# Base_SCH.net
KiCad netlist of a schematic drawn in Altium Designer
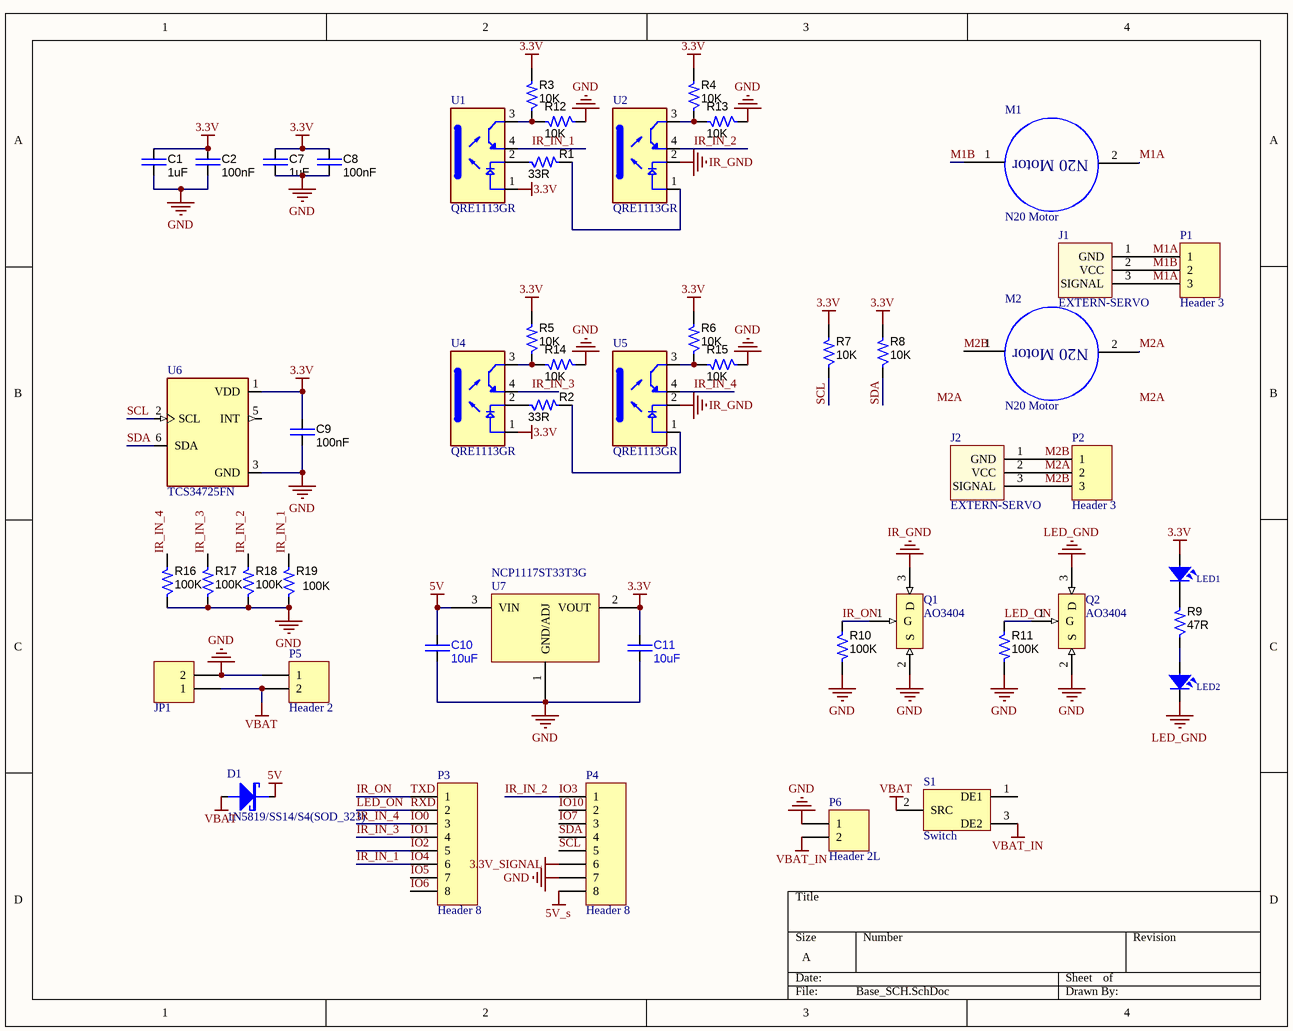
[diagram p0: Base_SCH.SchDoc]

(export (version "E")
  (design (tool "Eeschema 10.0.6"))
  (components
    (comp (ref "C1")
      (value "1uF")
      (footprint "CAPC1608X90N")
      (description "Capacitor SMD Cer 470nF 10% 16V X7R 0603")
      (fields (field (name "TOLERANCE") "±10%"))
      (libsource (lib "WIle_dev_kit") (part "CAP C_0603"))
    )
    (comp (ref "C2")
      (value "100nF")
      (footprint "CAPC1608X90N")
      (description "Capacitor SMD Cer 470nF 10% 16V X7R 0603")
      (fields (field (name "TOLERANCE") "±10%"))
      (libsource (lib "WIle_dev_kit") (part "CAP C_0603"))
    )
    (comp (ref "C7")
      (value "1uF")
      (footprint "CAPC1608X90N")
      (description "Capacitor SMD Cer 470nF 10% 16V X7R 0603")
      (fields (field (name "TOLERANCE") "±10%"))
      (libsource (lib "WIle_dev_kit") (part "CAP C_0603"))
    )
    (comp (ref "C8")
      (value "100nF")
      (footprint "CAPC1608X90N")
      (description "Capacitor SMD Cer 470nF 10% 16V X7R 0603")
      (fields (field (name "TOLERANCE") "±10%"))
      (libsource (lib "WIle_dev_kit") (part "CAP C_0603"))
    )
    (comp (ref "C9")
      (value "100nF")
      (footprint "CAPC1608X90N")
      (description "Capacitor SMD Cer 470nF 10% 16V X7R 0603")
      (fields (field (name "TOLERANCE") "±10%"))
      (libsource (lib "WIle_dev_kit") (part "CAP C_0603"))
    )
    (comp (ref "C10")
      (value "10uF")
      (footprint "CAPC2012X135N")
      (description "Capacitor SMD Cer 1.8nF 10% 50V X7R 0805")
      (fields (field (name "TOLERANCE") "±10%") (field (name "Comment") "approved sub OK"))
      (libsource (lib "WIle_dev_kit") (part "CAP C_0805"))
    )
    (comp (ref "C11")
      (value "10uF")
      (footprint "CAPC2012X135N")
      (description "Capacitor SMD Cer 1.8nF 10% 50V X7R 0805")
      (fields (field (name "TOLERANCE") "±10%") (field (name "Comment") "approved sub OK"))
      (libsource (lib "WIle_dev_kit") (part "CAP C_0805"))
    )
    (comp (ref "D1")
      (value "1N5819/SS14/S4(SOD_323)")
      (footprint "SMT_DIODE_SOD_323")
      (description "Surface mount schottky diode SOD-323(0805) Package")
      (libsource (lib "ad_via") (part "SMT_DIODE_SCHOTTKY_SOD_323"))
    )
    (comp (ref "J1")
      (value "EXTERN-SERVO")
      (footprint "JP3H")
      (libsource (lib "ad_via_motors") (part "EXTERN-SERVO"))
    )
    (comp (ref "J2")
      (value "EXTERN-SERVO")
      (footprint "JP3H")
      (libsource (lib "ad_via_motors") (part "EXTERN-SERVO"))
    )
    (comp (ref "JP1")
      (value "Header 2_1")
      (footprint "HED2")
      (description "Header, 2-Pin")
      (fields (field (name "MANUFACTURER") "Generic Components"))
      (libsource (lib "syhaunguyen") (part "Header 2_1"))
    )
    (comp (ref "LED1")
      (value "LED SMD")
      (footprint "SM-LED-0805-Orange")
      (libsource (lib "WIle_dev_kit") (part "LED SMD 0805"))
    )
    (comp (ref "LED2")
      (value "LED SMD")
      (footprint "SM-LED-0805-Orange")
      (libsource (lib "WIle_dev_kit") (part "LED SMD 0805"))
    )
    (comp (ref "M1")
      (value "N20 Motor")
      (footprint "N20 motor no header")
      (libsource (lib "WIle_dev_kit") (part "N20 Motor"))
    )
    (comp (ref "M2")
      (value "N20 Motor")
      (footprint "N20 motor no header")
      (libsource (lib "WIle_dev_kit") (part "N20 Motor"))
    )
    (comp (ref "P1")
      (value "Header 3")
      (footprint "HDR1X3")
      (description "Header, 3-Pin")
      (fields (field (name "PUBLISHER") "Altium Limited"))
      (libsource (lib "Miscellaneous Connectors") (part "Header 3"))
    )
    (comp (ref "P2")
      (value "Header 3")
      (footprint "HDR1X3")
      (description "Header, 3-Pin")
      (fields (field (name "PUBLISHER") "Altium Limited"))
      (libsource (lib "Miscellaneous Connectors") (part "Header 3"))
    )
    (comp (ref "P3")
      (value "Header 8")
      (footprint "HDR1X8")
      (description "Header, 8-Pin")
      (fields (field (name "PUBLISHER") "Altium Limited"))
      (libsource (lib "Miscellaneous Connectors") (part "Header 8"))
    )
    (comp (ref "P4")
      (value "Header 8")
      (footprint "HDR1X8")
      (description "Header, 8-Pin")
      (fields (field (name "PUBLISHER") "Altium Limited"))
      (libsource (lib "Miscellaneous Connectors") (part "Header 8"))
    )
    (comp (ref "P5")
      (value "Header 2")
      (footprint "HDR1X2")
      (description "Header, 2-Pin")
      (fields (field (name "PUBLISHER") "Altium Limited"))
      (libsource (lib "Miscellaneous Connectors") (part "Header 2"))
    )
    (comp (ref "P6")
      (value "Header 2L")
      (footprint "HDR1X2 - L")
      (description "Header, 2-Pin")
      (fields (field (name "PUBLISHER") "Altium Limited"))
      (libsource (lib "My Library") (part "Header 2L"))
    )
    (comp (ref "Q1") (value "AO3404") (footprint "SOT23-3") (libsource (lib "WIle_dev_kit") (part "AO3404")))
    (comp (ref "Q2") (value "AO3404") (footprint "SOT23-3") (libsource (lib "WIle_dev_kit") (part "AO3404")))
    (comp (ref "R1")
      (value "33R")
      (footprint "RESC1608N_ZERO")
      (description "Resistor SMD chip 0.0 Ohm 0.1W 0603")
      (fields (field (name "TOLERANCE") "±5%"))
      (libsource (lib "WIle_dev_kit") (part "RES_0603"))
    )
    (comp (ref "R2")
      (value "33R")
      (footprint "RESC1608N_ZERO")
      (description "Resistor SMD chip 0.0 Ohm 0.1W 0603")
      (fields (field (name "TOLERANCE") "±5%"))
      (libsource (lib "WIle_dev_kit") (part "RES_0603"))
    )
    (comp (ref "R3")
      (value "10K")
      (footprint "RESC1608N_ZERO")
      (description "Resistor SMD chip 0.0 Ohm 0.1W 0603")
      (fields (field (name "TOLERANCE") "±5%"))
      (libsource (lib "WIle_dev_kit") (part "RES_0603"))
    )
    (comp (ref "R4")
      (value "10K")
      (footprint "RESC1608N_ZERO")
      (description "Resistor SMD chip 0.0 Ohm 0.1W 0603")
      (fields (field (name "TOLERANCE") "±5%"))
      (libsource (lib "WIle_dev_kit") (part "RES_0603"))
    )
    (comp (ref "R5")
      (value "10K")
      (footprint "RESC1608N_ZERO")
      (description "Resistor SMD chip 0.0 Ohm 0.1W 0603")
      (fields (field (name "TOLERANCE") "±5%"))
      (libsource (lib "WIle_dev_kit") (part "RES_0603"))
    )
    (comp (ref "R6")
      (value "10K")
      (footprint "RESC1608N_ZERO")
      (description "Resistor SMD chip 0.0 Ohm 0.1W 0603")
      (fields (field (name "TOLERANCE") "±5%"))
      (libsource (lib "WIle_dev_kit") (part "RES_0603"))
    )
    (comp (ref "R7")
      (value "10K")
      (footprint "RESC1608N_ZERO")
      (description "Resistor SMD chip 0.0 Ohm 0.1W 0603")
      (fields (field (name "TOLERANCE") "±5%"))
      (libsource (lib "WIle_dev_kit") (part "RES_0603"))
    )
    (comp (ref "R8")
      (value "10K")
      (footprint "RESC1608N_ZERO")
      (description "Resistor SMD chip 0.0 Ohm 0.1W 0603")
      (fields (field (name "TOLERANCE") "±5%"))
      (libsource (lib "WIle_dev_kit") (part "RES_0603"))
    )
    (comp (ref "R9")
      (value "47R")
      (footprint "RESC1608N_ZERO")
      (description "Resistor SMD chip 0.0 Ohm 0.1W 0603")
      (fields (field (name "TOLERANCE") "±5%"))
      (libsource (lib "WIle_dev_kit") (part "RES_0603"))
    )
    (comp (ref "R10")
      (value "100K")
      (footprint "RESC1608N_ZERO")
      (description "Resistor SMD chip 0.0 Ohm 0.1W 0603")
      (fields (field (name "TOLERANCE") "±5%"))
      (libsource (lib "WIle_dev_kit") (part "RES_0603"))
    )
    (comp (ref "R11")
      (value "100K")
      (footprint "RESC1608N_ZERO")
      (description "Resistor SMD chip 0.0 Ohm 0.1W 0603")
      (fields (field (name "TOLERANCE") "±5%"))
      (libsource (lib "WIle_dev_kit") (part "RES_0603"))
    )
    (comp (ref "R12")
      (value "10K")
      (footprint "RESC1608N_ZERO")
      (description "Resistor SMD chip 0.0 Ohm 0.1W 0603")
      (fields (field (name "TOLERANCE") "±5%"))
      (libsource (lib "WIle_dev_kit") (part "RES_0603"))
    )
    (comp (ref "R13")
      (value "10K")
      (footprint "RESC1608N_ZERO")
      (description "Resistor SMD chip 0.0 Ohm 0.1W 0603")
      (fields (field (name "TOLERANCE") "±5%"))
      (libsource (lib "WIle_dev_kit") (part "RES_0603"))
    )
    (comp (ref "R14")
      (value "10K")
      (footprint "RESC1608N_ZERO")
      (description "Resistor SMD chip 0.0 Ohm 0.1W 0603")
      (fields (field (name "TOLERANCE") "±5%"))
      (libsource (lib "WIle_dev_kit") (part "RES_0603"))
    )
    (comp (ref "R15")
      (value "10K")
      (footprint "RESC1608N_ZERO")
      (description "Resistor SMD chip 0.0 Ohm 0.1W 0603")
      (fields (field (name "TOLERANCE") "±5%"))
      (libsource (lib "WIle_dev_kit") (part "RES_0603"))
    )
    (comp (ref "R16")
      (value "100K")
      (footprint "RESC1608N_ZERO")
      (description "Resistor SMD chip 0.0 Ohm 0.1W 0603")
      (fields (field (name "TOLERANCE") "±5%"))
      (libsource (lib "WIle_dev_kit") (part "RES_0603"))
    )
    (comp (ref "R17")
      (value "100K")
      (footprint "RESC1608N_ZERO")
      (description "Resistor SMD chip 0.0 Ohm 0.1W 0603")
      (fields (field (name "TOLERANCE") "±5%"))
      (libsource (lib "WIle_dev_kit") (part "RES_0603"))
    )
    (comp (ref "R18")
      (value "100K")
      (footprint "RESC1608N_ZERO")
      (description "Resistor SMD chip 0.0 Ohm 0.1W 0603")
      (fields (field (name "TOLERANCE") "±5%"))
      (libsource (lib "WIle_dev_kit") (part "RES_0603"))
    )
    (comp (ref "R19")
      (value "100K")
      (footprint "RESC1608N_ZERO")
      (description "Resistor SMD chip 0.0 Ohm 0.1W 0603")
      (fields (field (name "TOLERANCE") "±5%"))
      (libsource (lib "WIle_dev_kit") (part "RES_0603"))
    )
    (comp (ref "S1") (value "Switch") (footprint "Switch") (libsource (lib "My Library") (part "Switch")))
    (comp (ref "U1")
      (value "QRE1113GR")
      (footprint "SOIC180P460X187-4N")
      (description "Reflective Optical Sensor 0.039 (1mm) 4-SMD, Gull Wing")
      (fields (field (name "MF") "ON Semiconductor"))
      (libsource (lib "QRE1113GR") (part "QRE1113GR"))
    )
    (comp (ref "U2")
      (value "QRE1113GR")
      (footprint "SOIC180P460X187-4N")
      (description "Reflective Optical Sensor 0.039 (1mm) 4-SMD, Gull Wing")
      (fields (field (name "MF") "ON Semiconductor"))
      (libsource (lib "QRE1113GR") (part "QRE1113GR"))
    )
    (comp (ref "U4")
      (value "QRE1113GR")
      (footprint "SOIC180P460X187-4N")
      (description "Reflective Optical Sensor 0.039 (1mm) 4-SMD, Gull Wing")
      (fields (field (name "MF") "ON Semiconductor"))
      (libsource (lib "QRE1113GR") (part "QRE1113GR"))
    )
    (comp (ref "U5")
      (value "QRE1113GR")
      (footprint "SOIC180P460X187-4N")
      (description "Reflective Optical Sensor 0.039 (1mm) 4-SMD, Gull Wing")
      (fields (field (name "MF") "ON Semiconductor"))
      (libsource (lib "QRE1113GR") (part "QRE1113GR"))
    )
    (comp (ref "U6")
      (value "TCS34725FN")
      (footprint "SON65P200X240X70-6N")
      (description "ì»¬ëŸ¬ ì„¼ì„œ 16 b ê²Œì¸ ì œì–´, ì¸í„°ëŸ½íŠ¸, ì ˆì „ ëª¨ë“œ 6-SMD ëª¨ë“ˆ")
      (fields (field (name "MF") "ams"))
      (libsource (lib "TCS34725FN") (part "TCS34725FN"))
    )
    (comp (ref "U7")
      (value "NCP1117ST33T3G")
      (footprint "SOT-223 - duplicate")
      (description "NCP1117, NCV1117. 1.0 A Low-Dropout Positive  Fixed and Adjustable  Voltage Regulators")
      (libsource (lib "WIle_dev_kit") (part "NCP1117"))
    )
  )
  (nets
    (net (code "1") (name "/IO0") (class "Default")
      (node (ref "P3") (pin "3") (pinfunction "3_3") (pintype "passive"))
      (node (ref "R16") (pin "2") (pinfunction "2_2") (pintype "passive"))
      (node (ref "U5") (pin "4") (pinfunction "ET_4") (pintype "passive"))
    )
    (net (code "2") (name "/IO1") (class "Default")
      (node (ref "P3") (pin "4") (pinfunction "4_4") (pintype "passive"))
      (node (ref "R17") (pin "2") (pinfunction "2_2") (pintype "passive"))
      (node (ref "U4") (pin "4") (pinfunction "ET_4") (pintype "passive"))
    )
    (net (code "3") (name "/IO2") (class "Default")
      (node (ref "P3") (pin "5") (pinfunction "5_5") (pintype "passive"))
    )
    (net (code "4") (name "/IO3") (class "Default")
      (node (ref "P4") (pin "1") (pinfunction "1_1") (pintype "passive"))
      (node (ref "R18") (pin "2") (pinfunction "2_2") (pintype "passive"))
      (node (ref "U2") (pin "4") (pinfunction "ET_4") (pintype "passive"))
    )
    (net (code "5") (name "/IO4") (class "Default")
      (node (ref "P3") (pin "6") (pinfunction "6_6") (pintype "passive"))
      (node (ref "R19") (pin "2") (pinfunction "2_2") (pintype "passive"))
      (node (ref "U1") (pin "4") (pinfunction "ET_4") (pintype "passive"))
    )
    (net (code "6") (name "/IO5") (class "Default")
      (node (ref "P3") (pin "7") (pinfunction "7_7") (pintype "passive"))
    )
    (net (code "7") (name "/IO6") (class "Default")
      (node (ref "P3") (pin "8") (pinfunction "8_8") (pintype "passive"))
    )
    (net (code "8") (name "/IO7") (class "Default")
      (node (ref "P4") (pin "3") (pinfunction "3_3") (pintype "passive"))
    )
    (net (code "9") (name "/IO10") (class "Default")
      (node (ref "P4") (pin "2") (pinfunction "2_2") (pintype "passive"))
    )
    (net (code "10") (name "/IR_ON") (class "Default")
      (node (ref "P3") (pin "1") (pinfunction "1_1") (pintype "passive"))
      (node (ref "Q1") (pin "1") (pinfunction "G_1") (pintype "input"))
      (node (ref "R10") (pin "1") (pinfunction "1_1") (pintype "passive"))
    )
    (net (code "11") (name "/LED_ON") (class "Default")
      (node (ref "P3") (pin "2") (pinfunction "2_2") (pintype "passive"))
      (node (ref "Q2") (pin "1") (pinfunction "G_1") (pintype "input"))
      (node (ref "R11") (pin "1") (pinfunction "1_1") (pintype "passive"))
    )
    (net (code "12") (name "/M1A") (class "Default")
      (node (ref "J1") (pin "1") (pinfunction "GND_1") (pintype "passive"))
      (node (ref "J1") (pin "3") (pinfunction "SIGNAL_3") (pintype "passive"))
      (node (ref "M1") (pin "2") (pinfunction "0_2") (pintype "passive"))
      (node (ref "P1") (pin "1") (pinfunction "1_1") (pintype "passive"))
      (node (ref "P1") (pin "3") (pinfunction "3_3") (pintype "passive"))
    )
    (net (code "13") (name "/M1B") (class "Default")
      (node (ref "J1") (pin "2") (pinfunction "VCC_2") (pintype "passive"))
      (node (ref "M1") (pin "1") (pinfunction "1_1") (pintype "passive"))
      (node (ref "P1") (pin "2") (pinfunction "2_2") (pintype "passive"))
    )
    (net (code "14") (name "/M2A") (class "Default")
      (node (ref "J2") (pin "2") (pinfunction "VCC_2") (pintype "passive"))
      (node (ref "M2") (pin "2") (pinfunction "0_2") (pintype "passive"))
      (node (ref "P2") (pin "2") (pinfunction "2_2") (pintype "passive"))
    )
    (net (code "15") (name "/M2B") (class "Default")
      (node (ref "J2") (pin "1") (pinfunction "GND_1") (pintype "passive"))
      (node (ref "J2") (pin "3") (pinfunction "SIGNAL_3") (pintype "passive"))
      (node (ref "M2") (pin "1") (pinfunction "1_1") (pintype "passive"))
      (node (ref "P2") (pin "1") (pinfunction "1_1") (pintype "passive"))
      (node (ref "P2") (pin "3") (pinfunction "3_3") (pintype "passive"))
    )
    (net (code "16") (name "/SCL") (class "Default")
      (node (ref "P4") (pin "5") (pinfunction "5_5") (pintype "passive"))
      (node (ref "R7") (pin "1") (pinfunction "1_1") (pintype "passive"))
      (node (ref "U6") (pin "2") (pinfunction "SCL_2") (pintype "input"))
    )
    (net (code "17") (name "/SDA") (class "Default")
      (node (ref "P4") (pin "4") (pinfunction "4_4") (pintype "passive"))
      (node (ref "R8") (pin "1") (pinfunction "1_1") (pintype "passive"))
      (node (ref "U6") (pin "6") (pinfunction "SDA_6") (pintype "bidirectional"))
    )
    (net (code "18") (name "3.3V") (class "Default")
      (node (ref "C1") (pin "1") (pintype "passive"))
      (node (ref "C11") (pin "1") (pintype "passive"))
      (node (ref "C2") (pin "1") (pintype "passive"))
      (node (ref "C7") (pin "1") (pintype "passive"))
      (node (ref "C8") (pin "1") (pintype "passive"))
      (node (ref "C9") (pin "1") (pintype "passive"))
      (node (ref "LED1") (pin "1") (pinfunction "1_1") (pintype "passive"))
      (node (ref "R3") (pin "2") (pinfunction "2_2") (pintype "passive"))
      (node (ref "R4") (pin "2") (pinfunction "2_2") (pintype "passive"))
      (node (ref "R5") (pin "2") (pinfunction "2_2") (pintype "passive"))
      (node (ref "R6") (pin "2") (pinfunction "2_2") (pintype "passive"))
      (node (ref "R7") (pin "2") (pinfunction "2_2") (pintype "passive"))
      (node (ref "R8") (pin "2") (pinfunction "2_2") (pintype "passive"))
      (node (ref "U1") (pin "1") (pinfunction "A_1") (pintype "passive"))
      (node (ref "U4") (pin "1") (pinfunction "A_1") (pintype "passive"))
      (node (ref "U6") (pin "1") (pinfunction "VDD_1") (pintype "power_in"))
      (node (ref "U7") (pin "2") (pinfunction "VOUT_2") (pintype "passive"))
    )
    (net (code "19") (name "3.3V_SIGNAL") (class "Default")
      (node (ref "P4") (pin "6") (pinfunction "6_6") (pintype "passive"))
    )
    (net (code "20") (name "5V") (class "Default")
      (node (ref "C10") (pin "1") (pintype "passive"))
      (node (ref "D1") (pin "2") (pinfunction "K_2") (pintype "passive"))
      (node (ref "U7") (pin "3") (pinfunction "VIN_3") (pintype "passive"))
    )
    (net (code "21") (name "5V_s") (class "Default")
      (node (ref "P4") (pin "8") (pinfunction "8_8") (pintype "passive"))
    )
    (net (code "22") (name "GND") (class "Default")
      (node (ref "C1") (pin "2") (pintype "passive"))
      (node (ref "C10") (pin "2") (pintype "passive"))
      (node (ref "C11") (pin "2") (pintype "passive"))
      (node (ref "C2") (pin "2") (pintype "passive"))
      (node (ref "C7") (pin "2") (pintype "passive"))
      (node (ref "C8") (pin "2") (pintype "passive"))
      (node (ref "C9") (pin "2") (pintype "passive"))
      (node (ref "JP1") (pin "2") (pinfunction "2_2") (pintype "passive"))
      (node (ref "P4") (pin "7") (pinfunction "7_7") (pintype "passive"))
      (node (ref "P5") (pin "1") (pinfunction "1_1") (pintype "passive"))
      (node (ref "P6") (pin "1") (pinfunction "1_1") (pintype "passive"))
      (node (ref "Q1") (pin "2") (pinfunction "S_2") (pintype "input"))
      (node (ref "Q2") (pin "2") (pinfunction "S_2") (pintype "input"))
      (node (ref "R10") (pin "2") (pinfunction "2_2") (pintype "passive"))
      (node (ref "R11") (pin "2") (pinfunction "2_2") (pintype "passive"))
      (node (ref "R12") (pin "1") (pinfunction "1_1") (pintype "passive"))
      (node (ref "R13") (pin "1") (pinfunction "1_1") (pintype "passive"))
      (node (ref "R14") (pin "1") (pinfunction "1_1") (pintype "passive"))
      (node (ref "R15") (pin "1") (pinfunction "1_1") (pintype "passive"))
      (node (ref "R16") (pin "1") (pinfunction "1_1") (pintype "passive"))
      (node (ref "R17") (pin "1") (pinfunction "1_1") (pintype "passive"))
      (node (ref "R18") (pin "1") (pinfunction "1_1") (pintype "passive"))
      (node (ref "R19") (pin "1") (pinfunction "1_1") (pintype "passive"))
      (node (ref "U6") (pin "3") (pinfunction "GND_3") (pintype "power_in"))
      (node (ref "U7") (pin "1") (pinfunction "GND/ADJ_1") (pintype "passive"))
    )
    (net (code "23") (name "IR_GND") (class "Default")
      (node (ref "Q1") (pin "3") (pinfunction "D_3") (pintype "input"))
      (node (ref "U2") (pin "2") (pinfunction "C_2") (pintype "passive"))
      (node (ref "U5") (pin "2") (pinfunction "C_2") (pintype "passive"))
    )
    (net (code "24") (name "LED_GND") (class "Default")
      (node (ref "LED2") (pin "2") (pinfunction "2_2") (pintype "passive"))
      (node (ref "Q2") (pin "3") (pinfunction "D_3") (pintype "input"))
    )
    (net (code "25") (name "Net-(LED1-Pad2)") (class "Default")
      (node (ref "LED1") (pin "2") (pinfunction "2_2") (pintype "passive"))
      (node (ref "R9") (pin "2") (pinfunction "2_2") (pintype "passive"))
    )
    (net (code "26") (name "Net-(LED2-Pad1)") (class "Default")
      (node (ref "LED2") (pin "1") (pinfunction "1_1") (pintype "passive"))
      (node (ref "R9") (pin "1") (pinfunction "1_1") (pintype "passive"))
    )
    (net (code "27") (name "Net-(U1-C)") (class "Default")
      (node (ref "R1") (pin "1") (pinfunction "1_1") (pintype "passive"))
      (node (ref "U1") (pin "2") (pinfunction "C_2") (pintype "passive"))
    )
    (net (code "28") (name "Net-(U1-CT)") (class "Default")
      (node (ref "R12") (pin "2") (pinfunction "2_2") (pintype "passive"))
      (node (ref "R3") (pin "1") (pinfunction "1_1") (pintype "passive"))
      (node (ref "U1") (pin "3") (pinfunction "CT_3") (pintype "passive"))
    )
    (net (code "29") (name "Net-(U2-A)") (class "Default")
      (node (ref "R1") (pin "2") (pinfunction "2_2") (pintype "passive"))
      (node (ref "U2") (pin "1") (pinfunction "A_1") (pintype "passive"))
    )
    (net (code "30") (name "Net-(U2-CT)") (class "Default")
      (node (ref "R13") (pin "2") (pinfunction "2_2") (pintype "passive"))
      (node (ref "R4") (pin "1") (pinfunction "1_1") (pintype "passive"))
      (node (ref "U2") (pin "3") (pinfunction "CT_3") (pintype "passive"))
    )
    (net (code "31") (name "Net-(U4-C)") (class "Default")
      (node (ref "R2") (pin "1") (pinfunction "1_1") (pintype "passive"))
      (node (ref "U4") (pin "2") (pinfunction "C_2") (pintype "passive"))
    )
    (net (code "32") (name "Net-(U4-CT)") (class "Default")
      (node (ref "R14") (pin "2") (pinfunction "2_2") (pintype "passive"))
      (node (ref "R5") (pin "1") (pinfunction "1_1") (pintype "passive"))
      (node (ref "U4") (pin "3") (pinfunction "CT_3") (pintype "passive"))
    )
    (net (code "33") (name "Net-(U5-A)") (class "Default")
      (node (ref "R2") (pin "2") (pinfunction "2_2") (pintype "passive"))
      (node (ref "U5") (pin "1") (pinfunction "A_1") (pintype "passive"))
    )
    (net (code "34") (name "Net-(U5-CT)") (class "Default")
      (node (ref "R15") (pin "2") (pinfunction "2_2") (pintype "passive"))
      (node (ref "R6") (pin "1") (pinfunction "1_1") (pintype "passive"))
      (node (ref "U5") (pin "3") (pinfunction "CT_3") (pintype "passive"))
    )
    (net (code "35") (name "VBAT") (class "Default")
      (node (ref "D1") (pin "1") (pinfunction "A_1") (pintype "passive"))
      (node (ref "JP1") (pin "1") (pinfunction "1_1") (pintype "passive"))
      (node (ref "P5") (pin "2") (pinfunction "2_2") (pintype "passive"))
      (node (ref "S1") (pin "2") (pinfunction "SRC_2") (pintype "passive"))
    )
    (net (code "36") (name "VBAT_IN") (class "Default")
      (node (ref "P6") (pin "2") (pinfunction "2_2") (pintype "passive"))
      (node (ref "S1") (pin "3") (pinfunction "DE2_3") (pintype "passive"))
    )
    (net (code "37") (name "unconnected-(S1-DE1-Pad1)") (class "Default")
      (node (ref "S1") (pin "1") (pinfunction "DE1_1") (pintype "passive"))
    )
    (net (code "38") (name "unconnected-(S1-Pad4)") (class "Default")
      (node (ref "S1") (pin "4") (pinfunction "4_4") (pintype "passive"))
    )
    (net (code "39") (name "unconnected-(S1-Pad5)") (class "Default")
      (node (ref "S1") (pin "5") (pinfunction "5_5") (pintype "passive"))
    )
    (net (code "40") (name "unconnected-(U6-INT-Pad5)") (class "Default")
      (node (ref "U6") (pin "5") (pinfunction "INT_5") (pintype "output"))
    )
  )
)
